# Schematics.net
KiCad netlist of a schematic drawn in Altium Designer
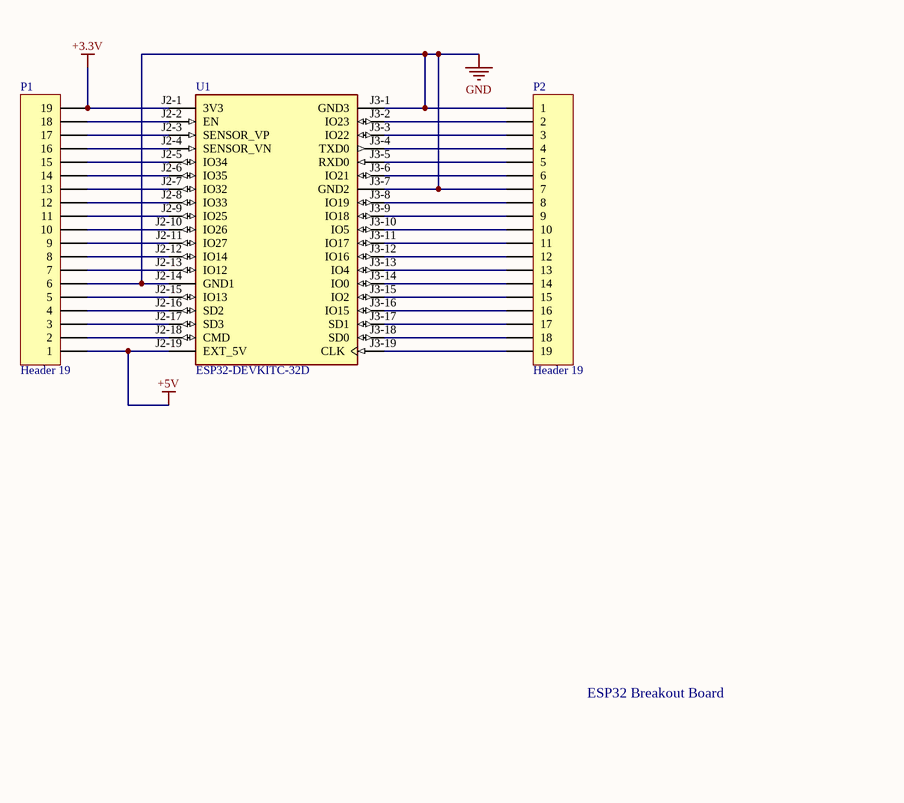
[diagram p0: Schematics.SchDoc]

(export (version "E")
  (design (tool "Eeschema 10.0.6"))
  (components
    (comp (ref "P1")
      (value "Header 19")
      (footprint "HDR1X19")
      (description "Header, 19-Pin")
      (fields (field (name "PUBLISHER") "Altium Limited"))
      (libsource (lib "") (part "Header 19_1"))
    )
    (comp (ref "P2")
      (value "Header 19")
      (footprint "HDR1X19")
      (description "Header, 19-Pin")
      (fields (field (name "PUBLISHER") "Altium Limited"))
      (libsource (lib "Miscellaneous Connectors") (part "Header 19"))
    )
    (comp (ref "U1")
      (value "ESP32-DEVKITC-32D")
      (footprint "MODULE_ESP32-DEVKITC-32D")
      (description "WiFi Development Tools (802.11) ESP32 General Development Kit, ESP32-WROOM-32D on the board")
      (fields (field (name "MF") "Espressif Systems"))
      (libsource (lib "ESP32-DEVKITC-32D") (part "ESP32-DEVKITC-32D"))
    )
  )
  (nets
    (net (code "1") (name "+3.3V") (class "Default")
      (node (ref "P1") (pin "19") (pinfunction "19_19") (pintype "passive"))
      (node (ref "U1") (pin "J2-1") (pinfunction "3V3_J2-1") (pintype "power_in"))
    )
    (net (code "2") (name "+5V") (class "Default")
      (node (ref "P1") (pin "1") (pinfunction "1_1") (pintype "passive"))
      (node (ref "U1") (pin "J2-19") (pinfunction "EXT_5V_J2-19") (pintype "power_in"))
    )
    (net (code "3") (name "GND") (class "Default")
      (node (ref "P1") (pin "6") (pinfunction "6_6") (pintype "passive"))
      (node (ref "P2") (pin "1") (pinfunction "1_1") (pintype "passive"))
      (node (ref "P2") (pin "7") (pinfunction "7_7") (pintype "passive"))
      (node (ref "U1") (pin "J2-14") (pinfunction "GND1_J2-14") (pintype "power_in"))
      (node (ref "U1") (pin "J3-1") (pinfunction "GND3_J3-1") (pintype "power_in"))
      (node (ref "U1") (pin "J3-7") (pinfunction "GND2_J3-7") (pintype "power_in"))
    )
    (net (code "4") (name "Net-(U1-CLK)") (class "Default")
      (node (ref "P2") (pin "19") (pinfunction "19_19") (pintype "passive"))
      (node (ref "U1") (pin "J3-19") (pinfunction "CLK_J3-19") (pintype "input"))
    )
    (net (code "5") (name "Net-(U1-CMD)") (class "Default")
      (node (ref "P1") (pin "2") (pinfunction "2_2") (pintype "passive"))
      (node (ref "U1") (pin "J2-18") (pinfunction "CMD_J2-18") (pintype "bidirectional"))
    )
    (net (code "6") (name "Net-(U1-EN)") (class "Default")
      (node (ref "P1") (pin "18") (pinfunction "18_18") (pintype "passive"))
      (node (ref "U1") (pin "J2-2") (pinfunction "EN_J2-2") (pintype "input"))
    )
    (net (code "7") (name "Net-(U1-IO0)") (class "Default")
      (node (ref "P2") (pin "14") (pinfunction "14_14") (pintype "passive"))
      (node (ref "U1") (pin "J3-14") (pinfunction "IO0_J3-14") (pintype "bidirectional"))
    )
    (net (code "8") (name "Net-(U1-IO2)") (class "Default")
      (node (ref "P2") (pin "15") (pinfunction "15_15") (pintype "passive"))
      (node (ref "U1") (pin "J3-15") (pinfunction "IO2_J3-15") (pintype "bidirectional"))
    )
    (net (code "9") (name "Net-(U1-IO4)") (class "Default")
      (node (ref "P2") (pin "13") (pinfunction "13_13") (pintype "passive"))
      (node (ref "U1") (pin "J3-13") (pinfunction "IO4_J3-13") (pintype "bidirectional"))
    )
    (net (code "10") (name "Net-(U1-IO5)") (class "Default")
      (node (ref "P2") (pin "10") (pinfunction "10_10") (pintype "passive"))
      (node (ref "U1") (pin "J3-10") (pinfunction "IO5_J3-10") (pintype "bidirectional"))
    )
    (net (code "11") (name "Net-(U1-IO12)") (class "Default")
      (node (ref "P1") (pin "7") (pinfunction "7_7") (pintype "passive"))
      (node (ref "U1") (pin "J2-13") (pinfunction "IO12_J2-13") (pintype "bidirectional"))
    )
    (net (code "12") (name "Net-(U1-IO13)") (class "Default")
      (node (ref "P1") (pin "5") (pinfunction "5_5") (pintype "passive"))
      (node (ref "U1") (pin "J2-15") (pinfunction "IO13_J2-15") (pintype "bidirectional"))
    )
    (net (code "13") (name "Net-(U1-IO14)") (class "Default")
      (node (ref "P1") (pin "8") (pinfunction "8_8") (pintype "passive"))
      (node (ref "U1") (pin "J2-12") (pinfunction "IO14_J2-12") (pintype "bidirectional"))
    )
    (net (code "14") (name "Net-(U1-IO15)") (class "Default")
      (node (ref "P2") (pin "16") (pinfunction "16_16") (pintype "passive"))
      (node (ref "U1") (pin "J3-16") (pinfunction "IO15_J3-16") (pintype "bidirectional"))
    )
    (net (code "15") (name "Net-(U1-IO16)") (class "Default")
      (node (ref "P2") (pin "12") (pinfunction "12_12") (pintype "passive"))
      (node (ref "U1") (pin "J3-12") (pinfunction "IO16_J3-12") (pintype "bidirectional"))
    )
    (net (code "16") (name "Net-(U1-IO17)") (class "Default")
      (node (ref "P2") (pin "11") (pinfunction "11_11") (pintype "passive"))
      (node (ref "U1") (pin "J3-11") (pinfunction "IO17_J3-11") (pintype "bidirectional"))
    )
    (net (code "17") (name "Net-(U1-IO18)") (class "Default")
      (node (ref "P2") (pin "9") (pinfunction "9_9") (pintype "passive"))
      (node (ref "U1") (pin "J3-9") (pinfunction "IO18_J3-9") (pintype "bidirectional"))
    )
    (net (code "18") (name "Net-(U1-IO19)") (class "Default")
      (node (ref "P2") (pin "8") (pinfunction "8_8") (pintype "passive"))
      (node (ref "U1") (pin "J3-8") (pinfunction "IO19_J3-8") (pintype "bidirectional"))
    )
    (net (code "19") (name "Net-(U1-IO21)") (class "Default")
      (node (ref "P2") (pin "6") (pinfunction "6_6") (pintype "passive"))
      (node (ref "U1") (pin "J3-6") (pinfunction "IO21_J3-6") (pintype "bidirectional"))
    )
    (net (code "20") (name "Net-(U1-IO22)") (class "Default")
      (node (ref "P2") (pin "3") (pinfunction "3_3") (pintype "passive"))
      (node (ref "U1") (pin "J3-3") (pinfunction "IO22_J3-3") (pintype "bidirectional"))
    )
    (net (code "21") (name "Net-(U1-IO23)") (class "Default")
      (node (ref "P2") (pin "2") (pinfunction "2_2") (pintype "passive"))
      (node (ref "U1") (pin "J3-2") (pinfunction "IO23_J3-2") (pintype "bidirectional"))
    )
    (net (code "22") (name "Net-(U1-IO25)") (class "Default")
      (node (ref "P1") (pin "11") (pinfunction "11_11") (pintype "passive"))
      (node (ref "U1") (pin "J2-9") (pinfunction "IO25_J2-9") (pintype "bidirectional"))
    )
    (net (code "23") (name "Net-(U1-IO26)") (class "Default")
      (node (ref "P1") (pin "10") (pinfunction "10_10") (pintype "passive"))
      (node (ref "U1") (pin "J2-10") (pinfunction "IO26_J2-10") (pintype "bidirectional"))
    )
    (net (code "24") (name "Net-(U1-IO27)") (class "Default")
      (node (ref "P1") (pin "9") (pinfunction "9_9") (pintype "passive"))
      (node (ref "U1") (pin "J2-11") (pinfunction "IO27_J2-11") (pintype "bidirectional"))
    )
    (net (code "25") (name "Net-(U1-IO32)") (class "Default")
      (node (ref "P1") (pin "13") (pinfunction "13_13") (pintype "passive"))
      (node (ref "U1") (pin "J2-7") (pinfunction "IO32_J2-7") (pintype "bidirectional"))
    )
    (net (code "26") (name "Net-(U1-IO33)") (class "Default")
      (node (ref "P1") (pin "12") (pinfunction "12_12") (pintype "passive"))
      (node (ref "U1") (pin "J2-8") (pinfunction "IO33_J2-8") (pintype "bidirectional"))
    )
    (net (code "27") (name "Net-(U1-IO34)") (class "Default")
      (node (ref "P1") (pin "15") (pinfunction "15_15") (pintype "passive"))
      (node (ref "U1") (pin "J2-5") (pinfunction "IO34_J2-5") (pintype "bidirectional"))
    )
    (net (code "28") (name "Net-(U1-IO35)") (class "Default")
      (node (ref "P1") (pin "14") (pinfunction "14_14") (pintype "passive"))
      (node (ref "U1") (pin "J2-6") (pinfunction "IO35_J2-6") (pintype "bidirectional"))
    )
    (net (code "29") (name "Net-(U1-RXD0)") (class "Default")
      (node (ref "P2") (pin "5") (pinfunction "5_5") (pintype "passive"))
      (node (ref "U1") (pin "J3-5") (pinfunction "RXD0_J3-5") (pintype "input"))
    )
    (net (code "30") (name "Net-(U1-SD0)") (class "Default")
      (node (ref "P2") (pin "18") (pinfunction "18_18") (pintype "passive"))
      (node (ref "U1") (pin "J3-18") (pinfunction "SD0_J3-18") (pintype "bidirectional"))
    )
    (net (code "31") (name "Net-(U1-SD1)") (class "Default")
      (node (ref "P2") (pin "17") (pinfunction "17_17") (pintype "passive"))
      (node (ref "U1") (pin "J3-17") (pinfunction "SD1_J3-17") (pintype "bidirectional"))
    )
    (net (code "32") (name "Net-(U1-SD2)") (class "Default")
      (node (ref "P1") (pin "4") (pinfunction "4_4") (pintype "passive"))
      (node (ref "U1") (pin "J2-16") (pinfunction "SD2_J2-16") (pintype "bidirectional"))
    )
    (net (code "33") (name "Net-(U1-SD3)") (class "Default")
      (node (ref "P1") (pin "3") (pinfunction "3_3") (pintype "passive"))
      (node (ref "U1") (pin "J2-17") (pinfunction "SD3_J2-17") (pintype "bidirectional"))
    )
    (net (code "34") (name "Net-(U1-SENSOR_VN)") (class "Default")
      (node (ref "P1") (pin "16") (pinfunction "16_16") (pintype "passive"))
      (node (ref "U1") (pin "J2-4") (pinfunction "SENSOR_VN_J2-4") (pintype "input"))
    )
    (net (code "35") (name "Net-(U1-SENSOR_VP)") (class "Default")
      (node (ref "P1") (pin "17") (pinfunction "17_17") (pintype "passive"))
      (node (ref "U1") (pin "J2-3") (pinfunction "SENSOR_VP_J2-3") (pintype "input"))
    )
    (net (code "36") (name "Net-(U1-TXD0)") (class "Default")
      (node (ref "P2") (pin "4") (pinfunction "4_4") (pintype "passive"))
      (node (ref "U1") (pin "J3-4") (pinfunction "TXD0_J3-4") (pintype "output"))
    )
  )
)
